# a.net
KiCad netlist of a schematic drawn in EAGLE
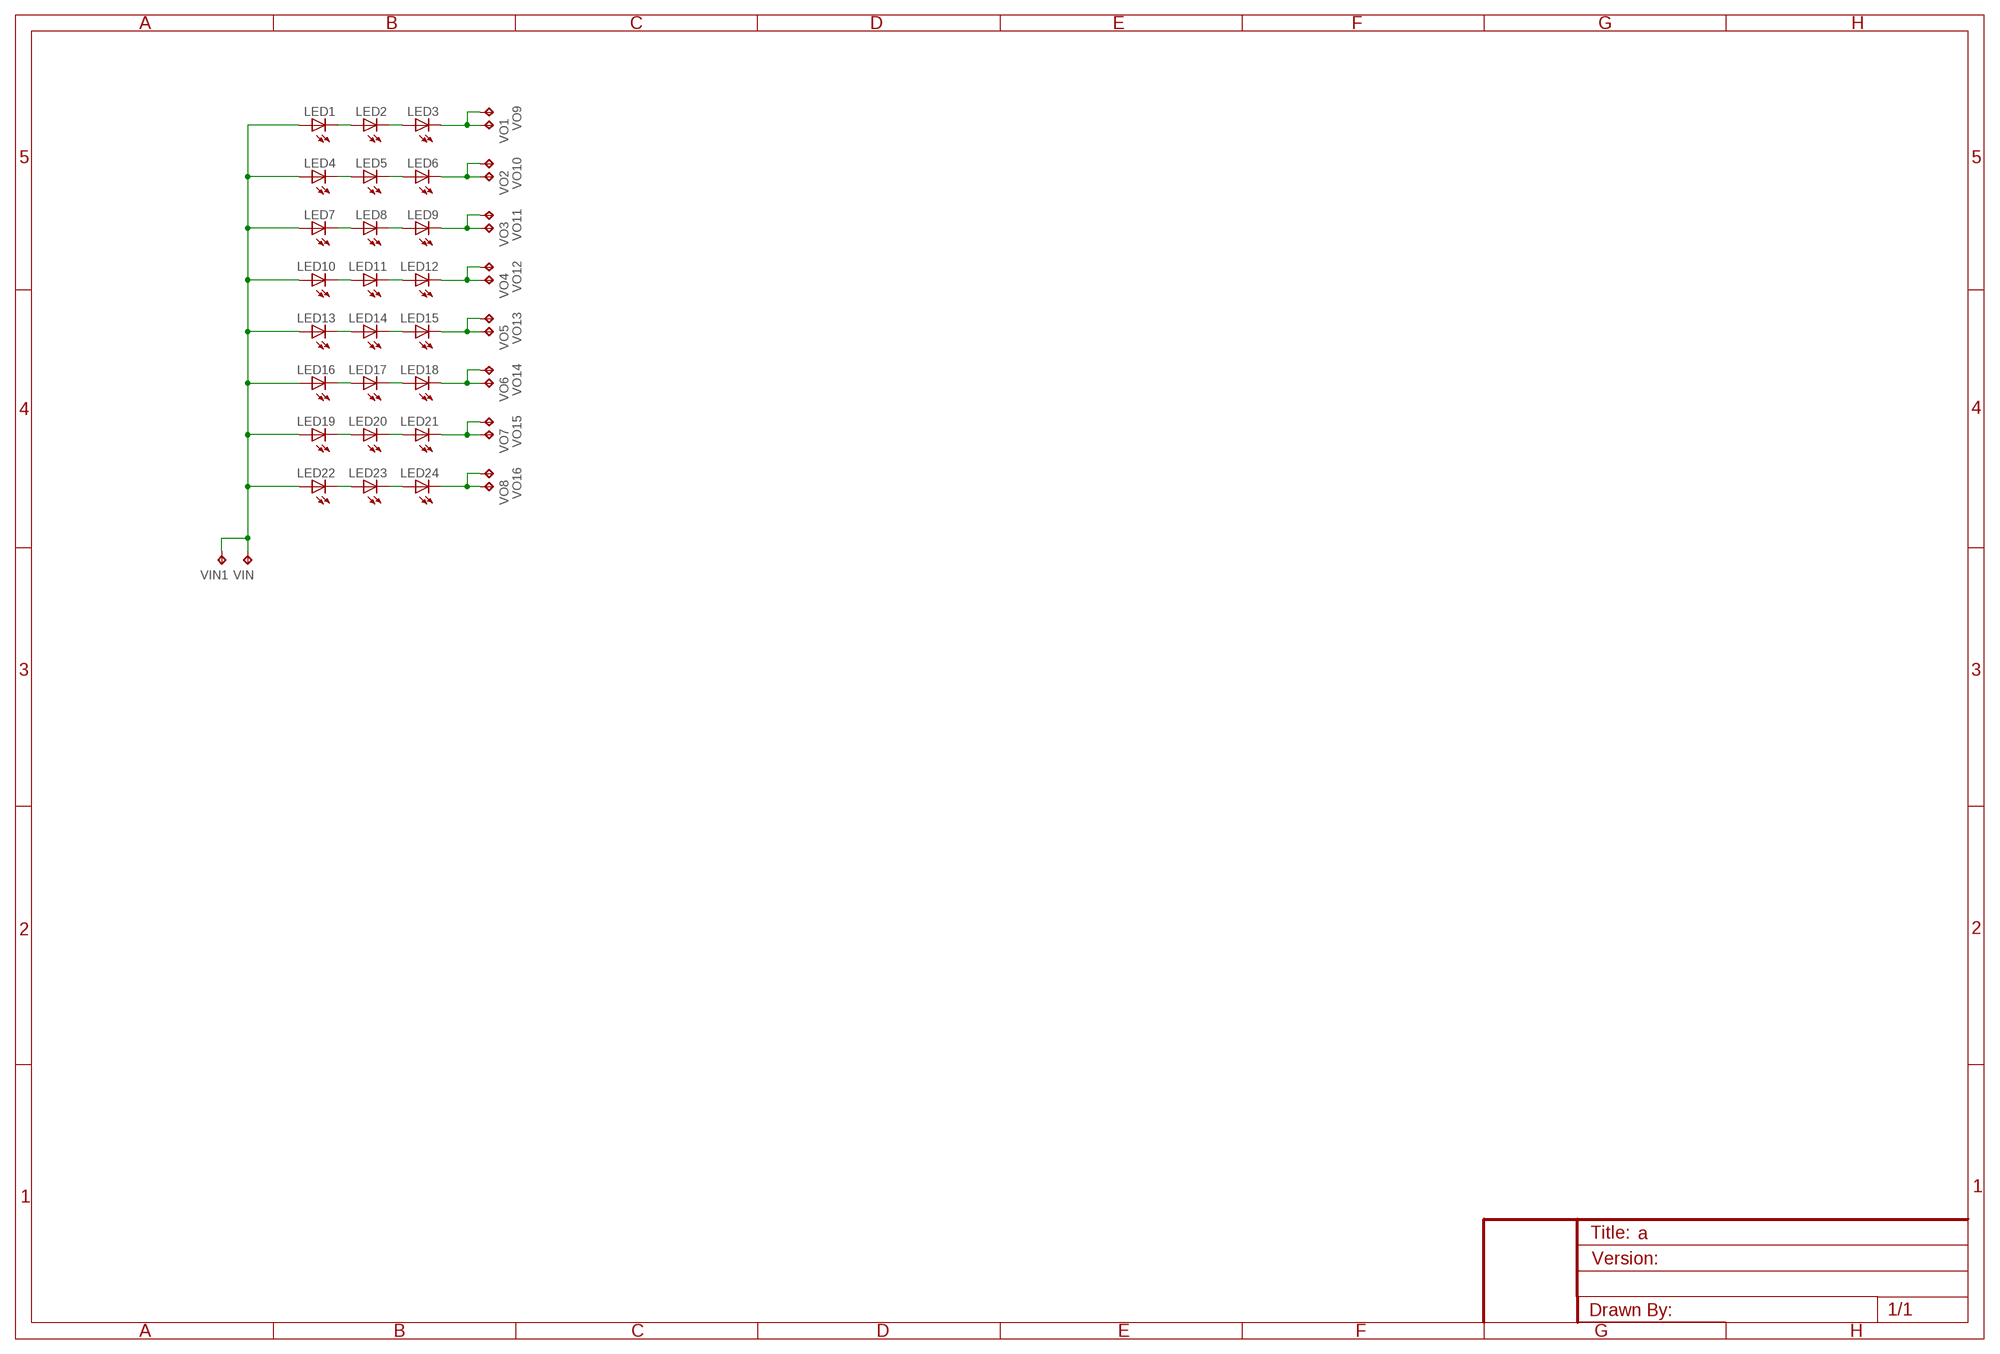
[diagram p0: schematic, sheet 1]

(export (version "E")
  (design (tool "Eeschema 10.0.6"))
  (components
    (comp (ref "LED1")
      (value "LED0805")
      (footprint "eagle-import:LED_0805")
      (libsource (lib "eagle-import") (part "LED0805"))
    )
    (comp (ref "LED2")
      (value "LED0805")
      (footprint "eagle-import:LED_0805")
      (libsource (lib "eagle-import") (part "LED0805"))
    )
    (comp (ref "LED3")
      (value "LED0805")
      (footprint "eagle-import:LED_0805")
      (libsource (lib "eagle-import") (part "LED0805"))
    )
    (comp (ref "LED4")
      (value "LED0805")
      (footprint "eagle-import:LED_0805")
      (libsource (lib "eagle-import") (part "LED0805"))
    )
    (comp (ref "LED5")
      (value "LED0805")
      (footprint "eagle-import:LED_0805")
      (libsource (lib "eagle-import") (part "LED0805"))
    )
    (comp (ref "LED6")
      (value "LED0805")
      (footprint "eagle-import:LED_0805")
      (libsource (lib "eagle-import") (part "LED0805"))
    )
    (comp (ref "LED7")
      (value "LED0805")
      (footprint "eagle-import:LED_0805")
      (libsource (lib "eagle-import") (part "LED0805"))
    )
    (comp (ref "LED8")
      (value "LED0805")
      (footprint "eagle-import:LED_0805")
      (libsource (lib "eagle-import") (part "LED0805"))
    )
    (comp (ref "LED9")
      (value "LED0805")
      (footprint "eagle-import:LED_0805")
      (libsource (lib "eagle-import") (part "LED0805"))
    )
    (comp (ref "LED10")
      (value "LED0805")
      (footprint "eagle-import:LED_0805")
      (libsource (lib "eagle-import") (part "LED0805"))
    )
    (comp (ref "LED11")
      (value "LED0805")
      (footprint "eagle-import:LED_0805")
      (libsource (lib "eagle-import") (part "LED0805"))
    )
    (comp (ref "LED12")
      (value "LED0805")
      (footprint "eagle-import:LED_0805")
      (libsource (lib "eagle-import") (part "LED0805"))
    )
    (comp (ref "LED13")
      (value "LED0805")
      (footprint "eagle-import:LED_0805")
      (libsource (lib "eagle-import") (part "LED0805"))
    )
    (comp (ref "LED14")
      (value "LED0805")
      (footprint "eagle-import:LED_0805")
      (libsource (lib "eagle-import") (part "LED0805"))
    )
    (comp (ref "LED15")
      (value "LED0805")
      (footprint "eagle-import:LED_0805")
      (libsource (lib "eagle-import") (part "LED0805"))
    )
    (comp (ref "LED16")
      (value "LED0805")
      (footprint "eagle-import:LED_0805")
      (libsource (lib "eagle-import") (part "LED0805"))
    )
    (comp (ref "LED17")
      (value "LED0805")
      (footprint "eagle-import:LED_0805")
      (libsource (lib "eagle-import") (part "LED0805"))
    )
    (comp (ref "LED18")
      (value "LED0805")
      (footprint "eagle-import:LED_0805")
      (libsource (lib "eagle-import") (part "LED0805"))
    )
    (comp (ref "LED19")
      (value "LED0805")
      (footprint "eagle-import:LED_0805")
      (libsource (lib "eagle-import") (part "LED0805"))
    )
    (comp (ref "LED20")
      (value "LED0805")
      (footprint "eagle-import:LED_0805")
      (libsource (lib "eagle-import") (part "LED0805"))
    )
    (comp (ref "LED21")
      (value "LED0805")
      (footprint "eagle-import:LED_0805")
      (libsource (lib "eagle-import") (part "LED0805"))
    )
    (comp (ref "LED22")
      (value "LED0805")
      (footprint "eagle-import:LED_0805")
      (libsource (lib "eagle-import") (part "LED0805"))
    )
    (comp (ref "LED23")
      (value "LED0805")
      (footprint "eagle-import:LED_0805")
      (libsource (lib "eagle-import") (part "LED0805"))
    )
    (comp (ref "LED24")
      (value "LED0805")
      (footprint "eagle-import:LED_0805")
      (libsource (lib "eagle-import") (part "LED0805"))
    )
    (comp (ref "VIN")
      (value "TEST_POINTPAD1-20")
      (footprint "eagle-import:P1-20")
      (libsource (lib "eagle-import") (part "TEST_POINTPAD1-20"))
    )
    (comp (ref "VIN1")
      (value "TEST_POINTPAD1-20")
      (footprint "eagle-import:P1-20")
      (libsource (lib "eagle-import") (part "TEST_POINTPAD1-20"))
    )
    (comp (ref "VO1")
      (value "TEST_POINTPAD1-20")
      (footprint "eagle-import:P1-20")
      (libsource (lib "eagle-import") (part "TEST_POINTPAD1-20"))
    )
    (comp (ref "VO2")
      (value "TEST_POINTPAD1-20")
      (footprint "eagle-import:P1-20")
      (libsource (lib "eagle-import") (part "TEST_POINTPAD1-20"))
    )
    (comp (ref "VO3")
      (value "TEST_POINTPAD1-20")
      (footprint "eagle-import:P1-20")
      (libsource (lib "eagle-import") (part "TEST_POINTPAD1-20"))
    )
    (comp (ref "VO4")
      (value "TEST_POINTPAD1-20")
      (footprint "eagle-import:P1-20")
      (libsource (lib "eagle-import") (part "TEST_POINTPAD1-20"))
    )
    (comp (ref "VO5")
      (value "TEST_POINTPAD1-20")
      (footprint "eagle-import:P1-20")
      (libsource (lib "eagle-import") (part "TEST_POINTPAD1-20"))
    )
    (comp (ref "VO6")
      (value "TEST_POINTPAD1-20")
      (footprint "eagle-import:P1-20")
      (libsource (lib "eagle-import") (part "TEST_POINTPAD1-20"))
    )
    (comp (ref "VO7")
      (value "TEST_POINTPAD1-20")
      (footprint "eagle-import:P1-20")
      (libsource (lib "eagle-import") (part "TEST_POINTPAD1-20"))
    )
    (comp (ref "VO8")
      (value "TEST_POINTPAD1-20")
      (footprint "eagle-import:P1-20")
      (libsource (lib "eagle-import") (part "TEST_POINTPAD1-20"))
    )
    (comp (ref "VO9")
      (value "TEST_POINTPAD1-20")
      (footprint "eagle-import:P1-20")
      (libsource (lib "eagle-import") (part "TEST_POINTPAD1-20"))
    )
    (comp (ref "VO10")
      (value "TEST_POINTPAD1-20")
      (footprint "eagle-import:P1-20")
      (libsource (lib "eagle-import") (part "TEST_POINTPAD1-20"))
    )
    (comp (ref "VO11")
      (value "TEST_POINTPAD1-20")
      (footprint "eagle-import:P1-20")
      (libsource (lib "eagle-import") (part "TEST_POINTPAD1-20"))
    )
    (comp (ref "VO12")
      (value "TEST_POINTPAD1-20")
      (footprint "eagle-import:P1-20")
      (libsource (lib "eagle-import") (part "TEST_POINTPAD1-20"))
    )
    (comp (ref "VO13")
      (value "TEST_POINTPAD1-20")
      (footprint "eagle-import:P1-20")
      (libsource (lib "eagle-import") (part "TEST_POINTPAD1-20"))
    )
    (comp (ref "VO14")
      (value "TEST_POINTPAD1-20")
      (footprint "eagle-import:P1-20")
      (libsource (lib "eagle-import") (part "TEST_POINTPAD1-20"))
    )
    (comp (ref "VO15")
      (value "TEST_POINTPAD1-20")
      (footprint "eagle-import:P1-20")
      (libsource (lib "eagle-import") (part "TEST_POINTPAD1-20"))
    )
    (comp (ref "VO16")
      (value "TEST_POINTPAD1-20")
      (footprint "eagle-import:P1-20")
      (libsource (lib "eagle-import") (part "TEST_POINTPAD1-20"))
    )
  )
  (nets
    (net (code "1") (name "Net-(LED1-PadA)") (class "Default")
      (node (ref "LED1") (pin "A") (pinfunction "A_A") (pintype "passive"))
      (node (ref "LED10") (pin "A") (pinfunction "A_A") (pintype "passive"))
      (node (ref "LED13") (pin "A") (pinfunction "A_A") (pintype "passive"))
      (node (ref "LED16") (pin "A") (pinfunction "A_A") (pintype "passive"))
      (node (ref "LED19") (pin "A") (pinfunction "A_A") (pintype "passive"))
      (node (ref "LED22") (pin "A") (pinfunction "A_A") (pintype "passive"))
      (node (ref "LED4") (pin "A") (pinfunction "A_A") (pintype "passive"))
      (node (ref "LED7") (pin "A") (pinfunction "A_A") (pintype "passive"))
      (node (ref "VIN") (pin "TP") (pinfunction "TP_TP") (pintype "input"))
      (node (ref "VIN1") (pin "TP") (pinfunction "TP_TP") (pintype "input"))
    )
    (net (code "2") (name "Net-(LED1-PadC)") (class "Default")
      (node (ref "LED1") (pin "C") (pinfunction "C_C") (pintype "passive"))
      (node (ref "LED2") (pin "A") (pinfunction "A_A") (pintype "passive"))
    )
    (net (code "3") (name "Net-(LED2-PadC)") (class "Default")
      (node (ref "LED2") (pin "C") (pinfunction "C_C") (pintype "passive"))
      (node (ref "LED3") (pin "A") (pinfunction "A_A") (pintype "passive"))
    )
    (net (code "4") (name "Net-(LED3-PadC)") (class "Default")
      (node (ref "LED3") (pin "C") (pinfunction "C_C") (pintype "passive"))
      (node (ref "VO1") (pin "TP") (pinfunction "TP_TP") (pintype "input"))
      (node (ref "VO9") (pin "TP") (pinfunction "TP_TP") (pintype "input"))
    )
    (net (code "5") (name "Net-(LED4-PadC)") (class "Default")
      (node (ref "LED4") (pin "C") (pinfunction "C_C") (pintype "passive"))
      (node (ref "LED5") (pin "A") (pinfunction "A_A") (pintype "passive"))
    )
    (net (code "6") (name "Net-(LED5-PadC)") (class "Default")
      (node (ref "LED5") (pin "C") (pinfunction "C_C") (pintype "passive"))
      (node (ref "LED6") (pin "A") (pinfunction "A_A") (pintype "passive"))
    )
    (net (code "7") (name "Net-(LED6-PadC)") (class "Default")
      (node (ref "LED6") (pin "C") (pinfunction "C_C") (pintype "passive"))
      (node (ref "VO10") (pin "TP") (pinfunction "TP_TP") (pintype "input"))
      (node (ref "VO2") (pin "TP") (pinfunction "TP_TP") (pintype "input"))
    )
    (net (code "8") (name "Net-(LED7-PadC)") (class "Default")
      (node (ref "LED7") (pin "C") (pinfunction "C_C") (pintype "passive"))
      (node (ref "LED8") (pin "A") (pinfunction "A_A") (pintype "passive"))
    )
    (net (code "9") (name "Net-(LED8-PadC)") (class "Default")
      (node (ref "LED8") (pin "C") (pinfunction "C_C") (pintype "passive"))
      (node (ref "LED9") (pin "A") (pinfunction "A_A") (pintype "passive"))
    )
    (net (code "10") (name "Net-(LED9-PadC)") (class "Default")
      (node (ref "LED9") (pin "C") (pinfunction "C_C") (pintype "passive"))
      (node (ref "VO11") (pin "TP") (pinfunction "TP_TP") (pintype "input"))
      (node (ref "VO3") (pin "TP") (pinfunction "TP_TP") (pintype "input"))
    )
    (net (code "11") (name "Net-(LED10-PadC)") (class "Default")
      (node (ref "LED10") (pin "C") (pinfunction "C_C") (pintype "passive"))
      (node (ref "LED11") (pin "A") (pinfunction "A_A") (pintype "passive"))
    )
    (net (code "12") (name "Net-(LED11-PadC)") (class "Default")
      (node (ref "LED11") (pin "C") (pinfunction "C_C") (pintype "passive"))
      (node (ref "LED12") (pin "A") (pinfunction "A_A") (pintype "passive"))
    )
    (net (code "13") (name "Net-(LED12-PadC)") (class "Default")
      (node (ref "LED12") (pin "C") (pinfunction "C_C") (pintype "passive"))
      (node (ref "VO12") (pin "TP") (pinfunction "TP_TP") (pintype "input"))
      (node (ref "VO4") (pin "TP") (pinfunction "TP_TP") (pintype "input"))
    )
    (net (code "14") (name "Net-(LED13-PadC)") (class "Default")
      (node (ref "LED13") (pin "C") (pinfunction "C_C") (pintype "passive"))
      (node (ref "LED14") (pin "A") (pinfunction "A_A") (pintype "passive"))
    )
    (net (code "15") (name "Net-(LED14-PadC)") (class "Default")
      (node (ref "LED14") (pin "C") (pinfunction "C_C") (pintype "passive"))
      (node (ref "LED15") (pin "A") (pinfunction "A_A") (pintype "passive"))
    )
    (net (code "16") (name "Net-(LED15-PadC)") (class "Default")
      (node (ref "LED15") (pin "C") (pinfunction "C_C") (pintype "passive"))
      (node (ref "VO13") (pin "TP") (pinfunction "TP_TP") (pintype "input"))
      (node (ref "VO5") (pin "TP") (pinfunction "TP_TP") (pintype "input"))
    )
    (net (code "17") (name "Net-(LED16-PadC)") (class "Default")
      (node (ref "LED16") (pin "C") (pinfunction "C_C") (pintype "passive"))
      (node (ref "LED17") (pin "A") (pinfunction "A_A") (pintype "passive"))
    )
    (net (code "18") (name "Net-(LED17-PadC)") (class "Default")
      (node (ref "LED17") (pin "C") (pinfunction "C_C") (pintype "passive"))
      (node (ref "LED18") (pin "A") (pinfunction "A_A") (pintype "passive"))
    )
    (net (code "19") (name "Net-(LED18-PadC)") (class "Default")
      (node (ref "LED18") (pin "C") (pinfunction "C_C") (pintype "passive"))
      (node (ref "VO14") (pin "TP") (pinfunction "TP_TP") (pintype "input"))
      (node (ref "VO6") (pin "TP") (pinfunction "TP_TP") (pintype "input"))
    )
    (net (code "20") (name "Net-(LED19-PadC)") (class "Default")
      (node (ref "LED19") (pin "C") (pinfunction "C_C") (pintype "passive"))
      (node (ref "LED20") (pin "A") (pinfunction "A_A") (pintype "passive"))
    )
    (net (code "21") (name "Net-(LED20-PadC)") (class "Default")
      (node (ref "LED20") (pin "C") (pinfunction "C_C") (pintype "passive"))
      (node (ref "LED21") (pin "A") (pinfunction "A_A") (pintype "passive"))
    )
    (net (code "22") (name "Net-(LED21-PadC)") (class "Default")
      (node (ref "LED21") (pin "C") (pinfunction "C_C") (pintype "passive"))
      (node (ref "VO15") (pin "TP") (pinfunction "TP_TP") (pintype "input"))
      (node (ref "VO7") (pin "TP") (pinfunction "TP_TP") (pintype "input"))
    )
    (net (code "23") (name "Net-(LED22-PadC)") (class "Default")
      (node (ref "LED22") (pin "C") (pinfunction "C_C") (pintype "passive"))
      (node (ref "LED23") (pin "A") (pinfunction "A_A") (pintype "passive"))
    )
    (net (code "24") (name "Net-(LED23-PadC)") (class "Default")
      (node (ref "LED23") (pin "C") (pinfunction "C_C") (pintype "passive"))
      (node (ref "LED24") (pin "A") (pinfunction "A_A") (pintype "passive"))
    )
    (net (code "25") (name "Net-(LED24-PadC)") (class "Default")
      (node (ref "LED24") (pin "C") (pinfunction "C_C") (pintype "passive"))
      (node (ref "VO16") (pin "TP") (pinfunction "TP_TP") (pintype "input"))
      (node (ref "VO8") (pin "TP") (pinfunction "TP_TP") (pintype "input"))
    )
  )
)
